# led_board.net
KiCad netlist of a schematic drawn in EAGLE
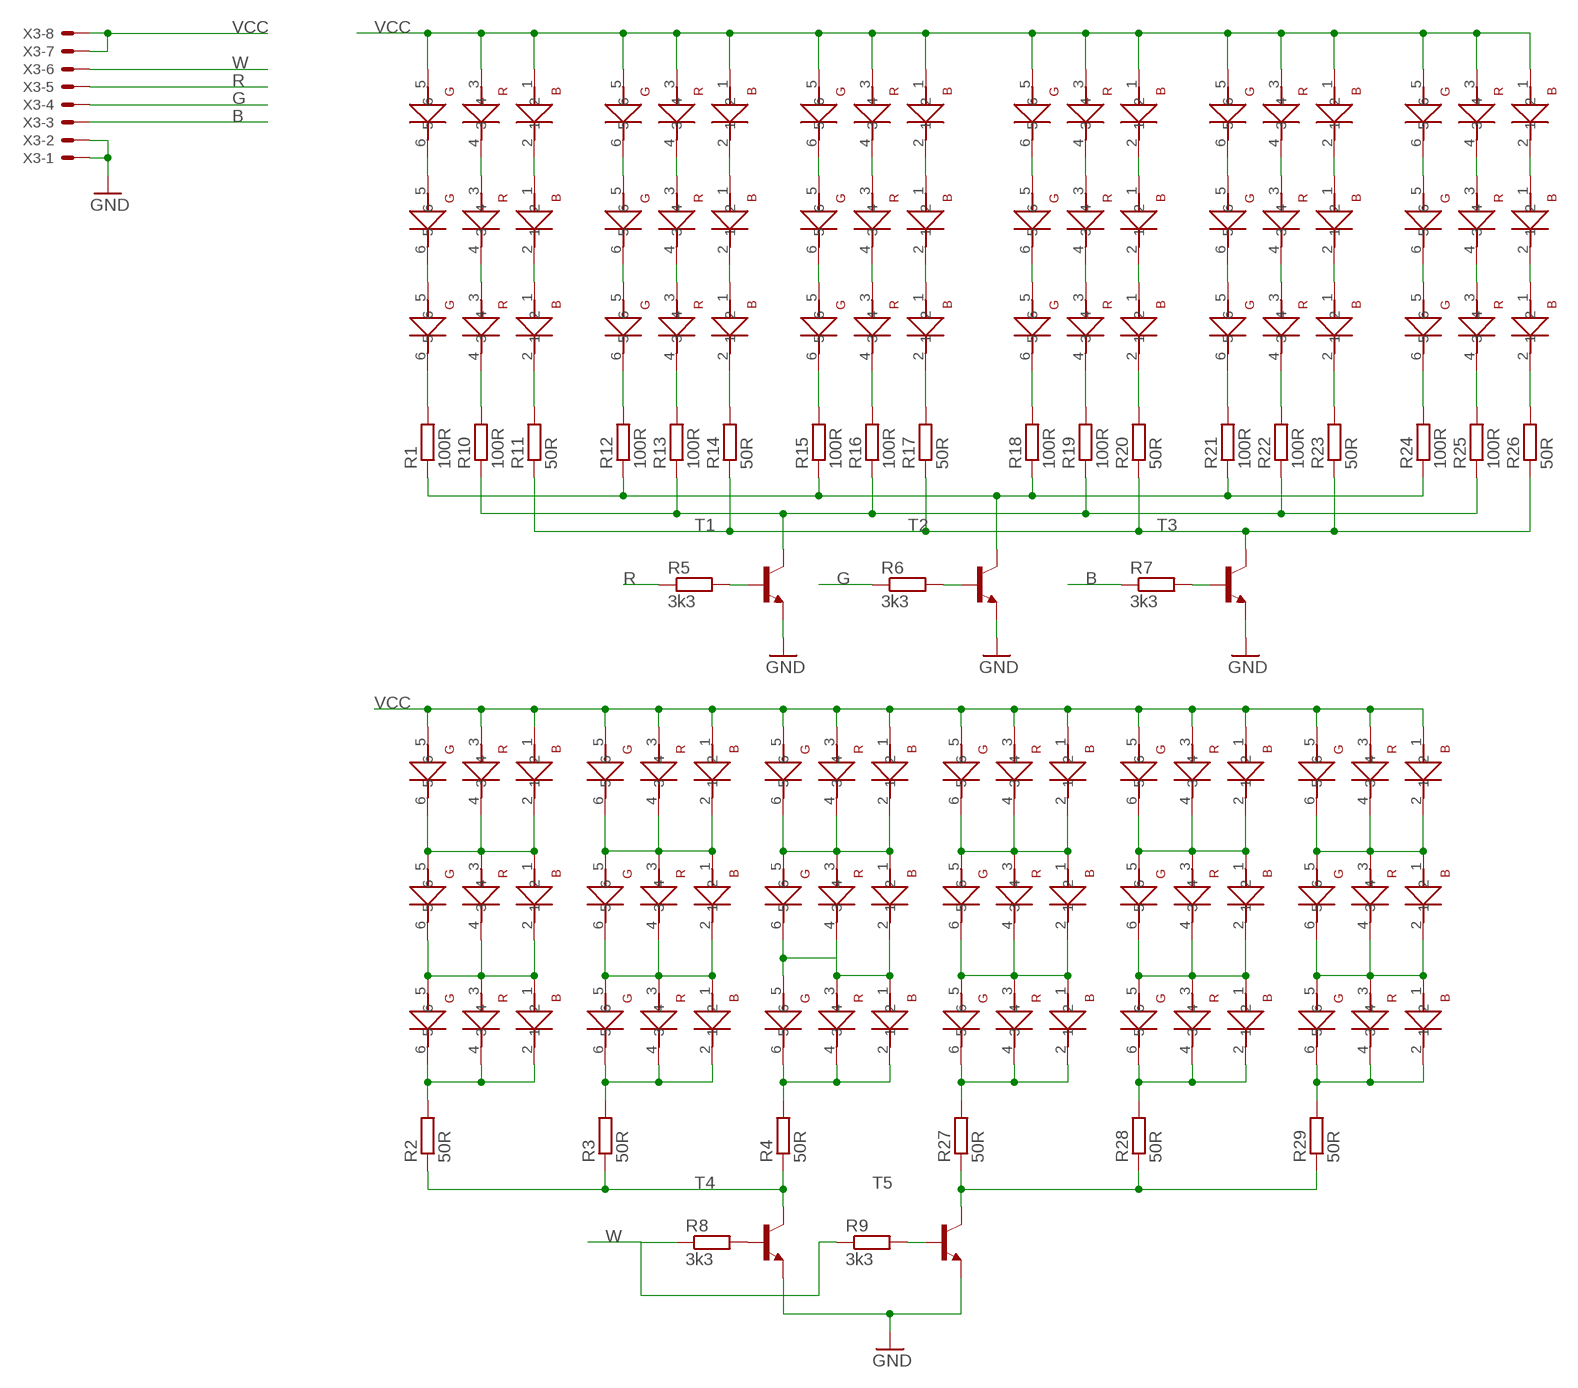
[diagram p0: schematic, sheet 1]

(export (version "E")
  (design (tool "Eeschema 10.0.6"))
  (components
    (comp (ref "R1")
      (value "100R")
      (footprint "eagle-import:M1206")
      (libsource (lib "eagle-import") (part "R-EU_M1206"))
    )
    (comp (ref "R2")
      (value "50R")
      (footprint "eagle-import:M1206")
      (libsource (lib "eagle-import") (part "R-EU_M1206"))
    )
    (comp (ref "R3")
      (value "50R")
      (footprint "eagle-import:M1206")
      (libsource (lib "eagle-import") (part "R-EU_M1206"))
    )
    (comp (ref "R4")
      (value "50R")
      (footprint "eagle-import:M1206")
      (libsource (lib "eagle-import") (part "R-EU_M1206"))
    )
    (comp (ref "R5")
      (value "3k3")
      (footprint "eagle-import:M1206")
      (libsource (lib "eagle-import") (part "R-EU_M1206"))
    )
    (comp (ref "R6")
      (value "3k3")
      (footprint "eagle-import:M1206")
      (libsource (lib "eagle-import") (part "R-EU_M1206"))
    )
    (comp (ref "R7")
      (value "3k3")
      (footprint "eagle-import:M1206")
      (libsource (lib "eagle-import") (part "R-EU_M1206"))
    )
    (comp (ref "R8")
      (value "3k3")
      (footprint "eagle-import:M1206")
      (libsource (lib "eagle-import") (part "R-EU_M1206"))
    )
    (comp (ref "R9")
      (value "3k3")
      (footprint "eagle-import:M1206")
      (libsource (lib "eagle-import") (part "R-EU_M1206"))
    )
    (comp (ref "R10")
      (value "100R")
      (footprint "eagle-import:M1206")
      (libsource (lib "eagle-import") (part "R-EU_M1206"))
    )
    (comp (ref "R11")
      (value "50R")
      (footprint "eagle-import:M1206")
      (libsource (lib "eagle-import") (part "R-EU_M1206"))
    )
    (comp (ref "R12")
      (value "100R")
      (footprint "eagle-import:M1206")
      (libsource (lib "eagle-import") (part "R-EU_M1206"))
    )
    (comp (ref "R13")
      (value "100R")
      (footprint "eagle-import:M1206")
      (libsource (lib "eagle-import") (part "R-EU_M1206"))
    )
    (comp (ref "R14")
      (value "50R")
      (footprint "eagle-import:M1206")
      (libsource (lib "eagle-import") (part "R-EU_M1206"))
    )
    (comp (ref "R15")
      (value "100R")
      (footprint "eagle-import:M1206")
      (libsource (lib "eagle-import") (part "R-EU_M1206"))
    )
    (comp (ref "R16")
      (value "100R")
      (footprint "eagle-import:M1206")
      (libsource (lib "eagle-import") (part "R-EU_M1206"))
    )
    (comp (ref "R17")
      (value "50R")
      (footprint "eagle-import:M1206")
      (libsource (lib "eagle-import") (part "R-EU_M1206"))
    )
    (comp (ref "R18")
      (value "100R")
      (footprint "eagle-import:M1206")
      (libsource (lib "eagle-import") (part "R-EU_M1206"))
    )
    (comp (ref "R19")
      (value "100R")
      (footprint "eagle-import:M1206")
      (libsource (lib "eagle-import") (part "R-EU_M1206"))
    )
    (comp (ref "R20")
      (value "50R")
      (footprint "eagle-import:M1206")
      (libsource (lib "eagle-import") (part "R-EU_M1206"))
    )
    (comp (ref "R21")
      (value "100R")
      (footprint "eagle-import:M1206")
      (libsource (lib "eagle-import") (part "R-EU_M1206"))
    )
    (comp (ref "R22")
      (value "100R")
      (footprint "eagle-import:M1206")
      (libsource (lib "eagle-import") (part "R-EU_M1206"))
    )
    (comp (ref "R23")
      (value "50R")
      (footprint "eagle-import:M1206")
      (libsource (lib "eagle-import") (part "R-EU_M1206"))
    )
    (comp (ref "R24")
      (value "100R")
      (footprint "eagle-import:M1206")
      (libsource (lib "eagle-import") (part "R-EU_M1206"))
    )
    (comp (ref "R25")
      (value "100R")
      (footprint "eagle-import:M1206")
      (libsource (lib "eagle-import") (part "R-EU_M1206"))
    )
    (comp (ref "R26")
      (value "50R")
      (footprint "eagle-import:M1206")
      (libsource (lib "eagle-import") (part "R-EU_M1206"))
    )
    (comp (ref "R27")
      (value "50R")
      (footprint "eagle-import:M1206")
      (libsource (lib "eagle-import") (part "R-EU_M1206"))
    )
    (comp (ref "R28")
      (value "50R")
      (footprint "eagle-import:M1206")
      (libsource (lib "eagle-import") (part "R-EU_M1206"))
    )
    (comp (ref "R29")
      (value "50R")
      (footprint "eagle-import:M1206")
      (libsource (lib "eagle-import") (part "R-EU_M1206"))
    )
    (comp (ref "T1")
      (value "-NPN-SOT223")
      (footprint "eagle-import:SOT223")
      (libsource (lib "eagle-import") (part "-NPN-SOT223"))
    )
    (comp (ref "T2")
      (value "-NPN-SOT223")
      (footprint "eagle-import:SOT223")
      (libsource (lib "eagle-import") (part "-NPN-SOT223"))
    )
    (comp (ref "T3")
      (value "-NPN-SOT223")
      (footprint "eagle-import:SOT223")
      (libsource (lib "eagle-import") (part "-NPN-SOT223"))
    )
    (comp (ref "T4")
      (value "-NPN-SOT223")
      (footprint "eagle-import:SOT223")
      (libsource (lib "eagle-import") (part "-NPN-SOT223"))
    )
    (comp (ref "T5")
      (value "-NPN-SOT223")
      (footprint "eagle-import:SOT223")
      (libsource (lib "eagle-import") (part "-NPN-SOT223"))
    )
    (comp (ref "U$1")
      (value "5050_LED")
      (footprint "eagle-import:5050_LED")
      (libsource (lib "eagle-import") (part "5050_LED"))
    )
    (comp (ref "U$2")
      (value "5050_LED")
      (footprint "eagle-import:5050_LED")
      (libsource (lib "eagle-import") (part "5050_LED"))
    )
    (comp (ref "U$3")
      (value "5050_LED")
      (footprint "eagle-import:5050_LED")
      (libsource (lib "eagle-import") (part "5050_LED"))
    )
    (comp (ref "U$4")
      (value "5050_LED")
      (footprint "eagle-import:5050_LED")
      (libsource (lib "eagle-import") (part "5050_LED"))
    )
    (comp (ref "U$5")
      (value "5050_LED")
      (footprint "eagle-import:5050_LED")
      (libsource (lib "eagle-import") (part "5050_LED"))
    )
    (comp (ref "U$6")
      (value "5050_LED")
      (footprint "eagle-import:5050_LED")
      (libsource (lib "eagle-import") (part "5050_LED"))
    )
    (comp (ref "U$7")
      (value "5050_LED")
      (footprint "eagle-import:5050_LED")
      (libsource (lib "eagle-import") (part "5050_LED"))
    )
    (comp (ref "U$8")
      (value "5050_LED")
      (footprint "eagle-import:5050_LED")
      (libsource (lib "eagle-import") (part "5050_LED"))
    )
    (comp (ref "U$9")
      (value "5050_LED")
      (footprint "eagle-import:5050_LED")
      (libsource (lib "eagle-import") (part "5050_LED"))
    )
    (comp (ref "U$10")
      (value "5050_LED")
      (footprint "eagle-import:5050_LED")
      (libsource (lib "eagle-import") (part "5050_LED"))
    )
    (comp (ref "U$11")
      (value "5050_LED")
      (footprint "eagle-import:5050_LED")
      (libsource (lib "eagle-import") (part "5050_LED"))
    )
    (comp (ref "U$12")
      (value "5050_LED")
      (footprint "eagle-import:5050_LED")
      (libsource (lib "eagle-import") (part "5050_LED"))
    )
    (comp (ref "U$13")
      (value "5050_LED")
      (footprint "eagle-import:5050_LED")
      (libsource (lib "eagle-import") (part "5050_LED"))
    )
    (comp (ref "U$14")
      (value "5050_LED")
      (footprint "eagle-import:5050_LED")
      (libsource (lib "eagle-import") (part "5050_LED"))
    )
    (comp (ref "U$15")
      (value "5050_LED")
      (footprint "eagle-import:5050_LED")
      (libsource (lib "eagle-import") (part "5050_LED"))
    )
    (comp (ref "U$16")
      (value "5050_LED")
      (footprint "eagle-import:5050_LED")
      (libsource (lib "eagle-import") (part "5050_LED"))
    )
    (comp (ref "U$17")
      (value "5050_LED")
      (footprint "eagle-import:5050_LED")
      (libsource (lib "eagle-import") (part "5050_LED"))
    )
    (comp (ref "U$18")
      (value "5050_LED")
      (footprint "eagle-import:5050_LED")
      (libsource (lib "eagle-import") (part "5050_LED"))
    )
    (comp (ref "U$19")
      (value "5050_LED")
      (footprint "eagle-import:5050_LED")
      (libsource (lib "eagle-import") (part "5050_LED"))
    )
    (comp (ref "U$20")
      (value "5050_LED")
      (footprint "eagle-import:5050_LED")
      (libsource (lib "eagle-import") (part "5050_LED"))
    )
    (comp (ref "U$21")
      (value "5050_LED")
      (footprint "eagle-import:5050_LED")
      (libsource (lib "eagle-import") (part "5050_LED"))
    )
    (comp (ref "U$22")
      (value "5050_LED")
      (footprint "eagle-import:5050_LED")
      (libsource (lib "eagle-import") (part "5050_LED"))
    )
    (comp (ref "U$23")
      (value "5050_LED")
      (footprint "eagle-import:5050_LED")
      (libsource (lib "eagle-import") (part "5050_LED"))
    )
    (comp (ref "U$24")
      (value "5050_LED")
      (footprint "eagle-import:5050_LED")
      (libsource (lib "eagle-import") (part "5050_LED"))
    )
    (comp (ref "U$25")
      (value "5050_LED")
      (footprint "eagle-import:5050_LED")
      (libsource (lib "eagle-import") (part "5050_LED"))
    )
    (comp (ref "U$26")
      (value "5050_LED")
      (footprint "eagle-import:5050_LED")
      (libsource (lib "eagle-import") (part "5050_LED"))
    )
    (comp (ref "U$27")
      (value "5050_LED")
      (footprint "eagle-import:5050_LED")
      (libsource (lib "eagle-import") (part "5050_LED"))
    )
    (comp (ref "U$28")
      (value "5050_LED")
      (footprint "eagle-import:5050_LED")
      (libsource (lib "eagle-import") (part "5050_LED"))
    )
    (comp (ref "U$29")
      (value "5050_LED")
      (footprint "eagle-import:5050_LED")
      (libsource (lib "eagle-import") (part "5050_LED"))
    )
    (comp (ref "U$30")
      (value "5050_LED")
      (footprint "eagle-import:5050_LED")
      (libsource (lib "eagle-import") (part "5050_LED"))
    )
    (comp (ref "U$31")
      (value "5050_LED")
      (footprint "eagle-import:5050_LED")
      (libsource (lib "eagle-import") (part "5050_LED"))
    )
    (comp (ref "U$32")
      (value "5050_LED")
      (footprint "eagle-import:5050_LED")
      (libsource (lib "eagle-import") (part "5050_LED"))
    )
    (comp (ref "U$33")
      (value "5050_LED")
      (footprint "eagle-import:5050_LED")
      (libsource (lib "eagle-import") (part "5050_LED"))
    )
    (comp (ref "U$34")
      (value "5050_LED")
      (footprint "eagle-import:5050_LED")
      (libsource (lib "eagle-import") (part "5050_LED"))
    )
    (comp (ref "U$35")
      (value "5050_LED")
      (footprint "eagle-import:5050_LED")
      (libsource (lib "eagle-import") (part "5050_LED"))
    )
    (comp (ref "U$38")
      (value "5050_LED")
      (footprint "eagle-import:5050_LED")
      (libsource (lib "eagle-import") (part "5050_LED"))
    )
    (comp (ref "X3")
      (value "KK-156-8")
      (footprint "eagle-import:KK-156-8")
      (fields (field (name "MF") "MOLEX"))
      (libsource (lib "eagle-import") (part "KK-156-8"))
    )
  )
  (nets
    (net (code "1") (name "/B") (class "Default")
      (node (ref "R7") (pin "1") (pinfunction "1_1") (pintype "passive"))
      (node (ref "X3") (pin "3") (pinfunction "S_3") (pintype "passive"))
    )
    (net (code "2") (name "/G") (class "Default")
      (node (ref "R6") (pin "1") (pinfunction "1_1") (pintype "passive"))
      (node (ref "X3") (pin "4") (pinfunction "S_4") (pintype "passive"))
    )
    (net (code "3") (name "/R") (class "Default")
      (node (ref "R5") (pin "1") (pinfunction "1_1") (pintype "passive"))
      (node (ref "X3") (pin "5") (pinfunction "S_5") (pintype "passive"))
    )
    (net (code "4") (name "/VCC") (class "Default")
      (node (ref "U$11") (pin "1") (pinfunction "1_1") (pintype "bidirectional"))
      (node (ref "U$11") (pin "3") (pinfunction "3_3") (pintype "bidirectional"))
      (node (ref "U$11") (pin "5") (pinfunction "5_5") (pintype "bidirectional"))
      (node (ref "U$14") (pin "1") (pinfunction "1_1") (pintype "bidirectional"))
      (node (ref "U$14") (pin "3") (pinfunction "3_3") (pintype "bidirectional"))
      (node (ref "U$14") (pin "5") (pinfunction "5_5") (pintype "bidirectional"))
      (node (ref "U$17") (pin "1") (pinfunction "1_1") (pintype "bidirectional"))
      (node (ref "U$17") (pin "3") (pinfunction "3_3") (pintype "bidirectional"))
      (node (ref "U$17") (pin "5") (pinfunction "5_5") (pintype "bidirectional"))
      (node (ref "U$18") (pin "1") (pinfunction "1_1") (pintype "bidirectional"))
      (node (ref "U$18") (pin "3") (pinfunction "3_3") (pintype "bidirectional"))
      (node (ref "U$18") (pin "5") (pinfunction "5_5") (pintype "bidirectional"))
      (node (ref "U$19") (pin "1") (pinfunction "1_1") (pintype "bidirectional"))
      (node (ref "U$19") (pin "3") (pinfunction "3_3") (pintype "bidirectional"))
      (node (ref "U$19") (pin "5") (pinfunction "5_5") (pintype "bidirectional"))
      (node (ref "U$2") (pin "1") (pinfunction "1_1") (pintype "bidirectional"))
      (node (ref "U$2") (pin "3") (pinfunction "3_3") (pintype "bidirectional"))
      (node (ref "U$2") (pin "5") (pinfunction "5_5") (pintype "bidirectional"))
      (node (ref "U$20") (pin "1") (pinfunction "1_1") (pintype "bidirectional"))
      (node (ref "U$20") (pin "3") (pinfunction "3_3") (pintype "bidirectional"))
      (node (ref "U$20") (pin "5") (pinfunction "5_5") (pintype "bidirectional"))
      (node (ref "U$21") (pin "1") (pinfunction "1_1") (pintype "bidirectional"))
      (node (ref "U$21") (pin "3") (pinfunction "3_3") (pintype "bidirectional"))
      (node (ref "U$21") (pin "5") (pinfunction "5_5") (pintype "bidirectional"))
      (node (ref "U$22") (pin "1") (pinfunction "1_1") (pintype "bidirectional"))
      (node (ref "U$22") (pin "3") (pinfunction "3_3") (pintype "bidirectional"))
      (node (ref "U$22") (pin "5") (pinfunction "5_5") (pintype "bidirectional"))
      (node (ref "U$34") (pin "1") (pinfunction "1_1") (pintype "bidirectional"))
      (node (ref "U$34") (pin "3") (pinfunction "3_3") (pintype "bidirectional"))
      (node (ref "U$34") (pin "5") (pinfunction "5_5") (pintype "bidirectional"))
      (node (ref "U$5") (pin "1") (pinfunction "1_1") (pintype "bidirectional"))
      (node (ref "U$5") (pin "3") (pinfunction "3_3") (pintype "bidirectional"))
      (node (ref "U$5") (pin "5") (pinfunction "5_5") (pintype "bidirectional"))
      (node (ref "U$8") (pin "1") (pinfunction "1_1") (pintype "bidirectional"))
      (node (ref "U$8") (pin "3") (pinfunction "3_3") (pintype "bidirectional"))
      (node (ref "U$8") (pin "5") (pinfunction "5_5") (pintype "bidirectional"))
      (node (ref "X3") (pin "7") (pinfunction "S_7") (pintype "passive"))
      (node (ref "X3") (pin "8") (pinfunction "S_8") (pintype "passive"))
    )
    (net (code "5") (name "/W") (class "Default")
      (node (ref "R8") (pin "1") (pinfunction "1_1") (pintype "passive"))
      (node (ref "R9") (pin "1") (pinfunction "1_1") (pintype "passive"))
      (node (ref "X3") (pin "6") (pinfunction "S_6") (pintype "passive"))
    )
    (net (code "6") (name "GND") (class "Default")
      (node (ref "T1") (pin "3") (pinfunction "E_3") (pintype "passive"))
      (node (ref "T2") (pin "3") (pinfunction "E_3") (pintype "passive"))
      (node (ref "T3") (pin "3") (pinfunction "E_3") (pintype "passive"))
      (node (ref "T4") (pin "3") (pinfunction "E_3") (pintype "passive"))
      (node (ref "T5") (pin "3") (pinfunction "E_3") (pintype "passive"))
      (node (ref "X3") (pin "1") (pinfunction "S_1") (pintype "passive"))
      (node (ref "X3") (pin "2") (pinfunction "S_2") (pintype "passive"))
    )
    (net (code "7") (name "Net-(R1-Pad2)") (class "Default")
      (node (ref "R1") (pin "2") (pinfunction "2_2") (pintype "passive"))
      (node (ref "U$1") (pin "6") (pinfunction "6_6") (pintype "bidirectional"))
    )
    (net (code "8") (name "Net-(R2-Pad2)") (class "Default")
      (node (ref "R2") (pin "2") (pinfunction "2_2") (pintype "passive"))
      (node (ref "U$29") (pin "2") (pinfunction "2_2") (pintype "bidirectional"))
      (node (ref "U$29") (pin "4") (pinfunction "4_4") (pintype "bidirectional"))
      (node (ref "U$29") (pin "6") (pinfunction "6_6") (pintype "bidirectional"))
    )
    (net (code "9") (name "Net-(R3-Pad2)") (class "Default")
      (node (ref "R3") (pin "2") (pinfunction "2_2") (pintype "passive"))
      (node (ref "U$30") (pin "2") (pinfunction "2_2") (pintype "bidirectional"))
      (node (ref "U$30") (pin "4") (pinfunction "4_4") (pintype "bidirectional"))
      (node (ref "U$30") (pin "6") (pinfunction "6_6") (pintype "bidirectional"))
    )
    (net (code "10") (name "Net-(R4-Pad2)") (class "Default")
      (node (ref "R4") (pin "2") (pinfunction "2_2") (pintype "passive"))
      (node (ref "U$31") (pin "2") (pinfunction "2_2") (pintype "bidirectional"))
      (node (ref "U$31") (pin "4") (pinfunction "4_4") (pintype "bidirectional"))
      (node (ref "U$31") (pin "6") (pinfunction "6_6") (pintype "bidirectional"))
    )
    (net (code "11") (name "Net-(R10-Pad2)") (class "Default")
      (node (ref "R10") (pin "2") (pinfunction "2_2") (pintype "passive"))
      (node (ref "U$1") (pin "4") (pinfunction "4_4") (pintype "bidirectional"))
    )
    (net (code "12") (name "Net-(R11-Pad2)") (class "Default")
      (node (ref "R11") (pin "2") (pinfunction "2_2") (pintype "passive"))
      (node (ref "U$1") (pin "2") (pinfunction "2_2") (pintype "bidirectional"))
    )
    (net (code "13") (name "Net-(R12-Pad2)") (class "Default")
      (node (ref "R12") (pin "2") (pinfunction "2_2") (pintype "passive"))
      (node (ref "U$4") (pin "6") (pinfunction "6_6") (pintype "bidirectional"))
    )
    (net (code "14") (name "Net-(R13-Pad2)") (class "Default")
      (node (ref "R13") (pin "2") (pinfunction "2_2") (pintype "passive"))
      (node (ref "U$4") (pin "4") (pinfunction "4_4") (pintype "bidirectional"))
    )
    (net (code "15") (name "Net-(R14-Pad2)") (class "Default")
      (node (ref "R14") (pin "2") (pinfunction "2_2") (pintype "passive"))
      (node (ref "U$4") (pin "2") (pinfunction "2_2") (pintype "bidirectional"))
    )
    (net (code "16") (name "Net-(R15-Pad2)") (class "Default")
      (node (ref "R15") (pin "2") (pinfunction "2_2") (pintype "passive"))
      (node (ref "U$7") (pin "6") (pinfunction "6_6") (pintype "bidirectional"))
    )
    (net (code "17") (name "Net-(R16-Pad2)") (class "Default")
      (node (ref "R16") (pin "2") (pinfunction "2_2") (pintype "passive"))
      (node (ref "U$7") (pin "4") (pinfunction "4_4") (pintype "bidirectional"))
    )
    (net (code "18") (name "Net-(R17-Pad2)") (class "Default")
      (node (ref "R17") (pin "2") (pinfunction "2_2") (pintype "passive"))
      (node (ref "U$7") (pin "2") (pinfunction "2_2") (pintype "bidirectional"))
    )
    (net (code "19") (name "Net-(R18-Pad2)") (class "Default")
      (node (ref "R18") (pin "2") (pinfunction "2_2") (pintype "passive"))
      (node (ref "U$10") (pin "6") (pinfunction "6_6") (pintype "bidirectional"))
    )
    (net (code "20") (name "Net-(R19-Pad2)") (class "Default")
      (node (ref "R19") (pin "2") (pinfunction "2_2") (pintype "passive"))
      (node (ref "U$10") (pin "4") (pinfunction "4_4") (pintype "bidirectional"))
    )
    (net (code "21") (name "Net-(R20-Pad2)") (class "Default")
      (node (ref "R20") (pin "2") (pinfunction "2_2") (pintype "passive"))
      (node (ref "U$10") (pin "2") (pinfunction "2_2") (pintype "bidirectional"))
    )
    (net (code "22") (name "Net-(R21-Pad2)") (class "Default")
      (node (ref "R21") (pin "2") (pinfunction "2_2") (pintype "passive"))
      (node (ref "U$13") (pin "6") (pinfunction "6_6") (pintype "bidirectional"))
    )
    (net (code "23") (name "Net-(R22-Pad2)") (class "Default")
      (node (ref "R22") (pin "2") (pinfunction "2_2") (pintype "passive"))
      (node (ref "U$13") (pin "4") (pinfunction "4_4") (pintype "bidirectional"))
    )
    (net (code "24") (name "Net-(R23-Pad2)") (class "Default")
      (node (ref "R23") (pin "2") (pinfunction "2_2") (pintype "passive"))
      (node (ref "U$13") (pin "2") (pinfunction "2_2") (pintype "bidirectional"))
    )
    (net (code "25") (name "Net-(R24-Pad2)") (class "Default")
      (node (ref "R24") (pin "2") (pinfunction "2_2") (pintype "passive"))
      (node (ref "U$16") (pin "6") (pinfunction "6_6") (pintype "bidirectional"))
    )
    (net (code "26") (name "Net-(R25-Pad2)") (class "Default")
      (node (ref "R25") (pin "2") (pinfunction "2_2") (pintype "passive"))
      (node (ref "U$16") (pin "4") (pinfunction "4_4") (pintype "bidirectional"))
    )
    (net (code "27") (name "Net-(R26-Pad2)") (class "Default")
      (node (ref "R26") (pin "2") (pinfunction "2_2") (pintype "passive"))
      (node (ref "U$16") (pin "2") (pinfunction "2_2") (pintype "bidirectional"))
    )
    (net (code "28") (name "Net-(R27-Pad2)") (class "Default")
      (node (ref "R27") (pin "2") (pinfunction "2_2") (pintype "passive"))
      (node (ref "U$32") (pin "2") (pinfunction "2_2") (pintype "bidirectional"))
      (node (ref "U$32") (pin "4") (pinfunction "4_4") (pintype "bidirectional"))
      (node (ref "U$32") (pin "6") (pinfunction "6_6") (pintype "bidirectional"))
    )
    (net (code "29") (name "Net-(R28-Pad2)") (class "Default")
      (node (ref "R28") (pin "2") (pinfunction "2_2") (pintype "passive"))
      (node (ref "U$33") (pin "2") (pinfunction "2_2") (pintype "bidirectional"))
      (node (ref "U$33") (pin "4") (pinfunction "4_4") (pintype "bidirectional"))
      (node (ref "U$33") (pin "6") (pinfunction "6_6") (pintype "bidirectional"))
    )
    (net (code "30") (name "Net-(R29-Pad2)") (class "Default")
      (node (ref "R29") (pin "2") (pinfunction "2_2") (pintype "passive"))
      (node (ref "U$35") (pin "2") (pinfunction "2_2") (pintype "bidirectional"))
      (node (ref "U$35") (pin "4") (pinfunction "4_4") (pintype "bidirectional"))
      (node (ref "U$35") (pin "6") (pinfunction "6_6") (pintype "bidirectional"))
    )
    (net (code "31") (name "Net-(T1-B)") (class "Default")
      (node (ref "R5") (pin "2") (pinfunction "2_2") (pintype "passive"))
      (node (ref "T1") (pin "1") (pinfunction "B_1") (pintype "passive"))
    )
    (net (code "32") (name "Net-(T1-C)") (class "Default")
      (node (ref "R10") (pin "1") (pinfunction "1_1") (pintype "passive"))
      (node (ref "R13") (pin "1") (pinfunction "1_1") (pintype "passive"))
      (node (ref "R16") (pin "1") (pinfunction "1_1") (pintype "passive"))
      (node (ref "R19") (pin "1") (pinfunction "1_1") (pintype "passive"))
      (node (ref "R22") (pin "1") (pinfunction "1_1") (pintype "passive"))
      (node (ref "R25") (pin "1") (pinfunction "1_1") (pintype "passive"))
      (node (ref "T1") (pin "4") (pinfunction "C_4") (pintype "passive"))
    )
    (net (code "33") (name "Net-(T2-B)") (class "Default")
      (node (ref "R6") (pin "2") (pinfunction "2_2") (pintype "passive"))
      (node (ref "T2") (pin "1") (pinfunction "B_1") (pintype "passive"))
    )
    (net (code "34") (name "Net-(T2-C)") (class "Default")
      (node (ref "R1") (pin "1") (pinfunction "1_1") (pintype "passive"))
      (node (ref "R12") (pin "1") (pinfunction "1_1") (pintype "passive"))
      (node (ref "R15") (pin "1") (pinfunction "1_1") (pintype "passive"))
      (node (ref "R18") (pin "1") (pinfunction "1_1") (pintype "passive"))
      (node (ref "R21") (pin "1") (pinfunction "1_1") (pintype "passive"))
      (node (ref "R24") (pin "1") (pinfunction "1_1") (pintype "passive"))
      (node (ref "T2") (pin "4") (pinfunction "C_4") (pintype "passive"))
    )
    (net (code "35") (name "Net-(T3-B)") (class "Default")
      (node (ref "R7") (pin "2") (pinfunction "2_2") (pintype "passive"))
      (node (ref "T3") (pin "1") (pinfunction "B_1") (pintype "passive"))
    )
    (net (code "36") (name "Net-(T3-C)") (class "Default")
      (node (ref "R11") (pin "1") (pinfunction "1_1") (pintype "passive"))
      (node (ref "R14") (pin "1") (pinfunction "1_1") (pintype "passive"))
      (node (ref "R17") (pin "1") (pinfunction "1_1") (pintype "passive"))
      (node (ref "R20") (pin "1") (pinfunction "1_1") (pintype "passive"))
      (node (ref "R23") (pin "1") (pinfunction "1_1") (pintype "passive"))
      (node (ref "R26") (pin "1") (pinfunction "1_1") (pintype "passive"))
      (node (ref "T3") (pin "4") (pinfunction "C_4") (pintype "passive"))
    )
    (net (code "37") (name "Net-(T4-B)") (class "Default")
      (node (ref "R8") (pin "2") (pinfunction "2_2") (pintype "passive"))
      (node (ref "T4") (pin "1") (pinfunction "B_1") (pintype "passive"))
    )
    (net (code "38") (name "Net-(T4-C)") (class "Default")
      (node (ref "R2") (pin "1") (pinfunction "1_1") (pintype "passive"))
      (node (ref "R3") (pin "1") (pinfunction "1_1") (pintype "passive"))
      (node (ref "R4") (pin "1") (pinfunction "1_1") (pintype "passive"))
      (node (ref "T4") (pin "4") (pinfunction "C_4") (pintype "passive"))
    )
    (net (code "39") (name "Net-(T5-B)") (class "Default")
      (node (ref "R9") (pin "2") (pinfunction "2_2") (pintype "passive"))
      (node (ref "T5") (pin "1") (pinfunction "B_1") (pintype "passive"))
    )
    (net (code "40") (name "Net-(T5-C)") (class "Default")
      (node (ref "R27") (pin "1") (pinfunction "1_1") (pintype "passive"))
      (node (ref "R28") (pin "1") (pinfunction "1_1") (pintype "passive"))
      (node (ref "R29") (pin "1") (pinfunction "1_1") (pintype "passive"))
      (node (ref "T5") (pin "4") (pinfunction "C_4") (pintype "passive"))
    )
    (net (code "41") (name "Net-(U$1-Pad1)") (class "Default")
      (node (ref "U$1") (pin "1") (pinfunction "1_1") (pintype "bidirectional"))
      (node (ref "U$38") (pin "2") (pinfunction "2_2") (pintype "bidirectional"))
    )
    (net (code "42") (name "Net-(U$1-Pad3)") (class "Default")
      (node (ref "U$1") (pin "3") (pinfunction "3_3") (pintype "bidirectional"))
      (node (ref "U$38") (pin "4") (pinfunction "4_4") (pintype "bidirectional"))
    )
    (net (code "43") (name "Net-(U$1-Pad5)") (class "Default")
      (node (ref "U$1") (pin "5") (pinfunction "5_5") (pintype "bidirectional"))
      (node (ref "U$38") (pin "6") (pinfunction "6_6") (pintype "bidirectional"))
    )
    (net (code "44") (name "Net-(U$2-Pad2)") (class "Default")
      (node (ref "U$2") (pin "2") (pinfunction "2_2") (pintype "bidirectional"))
      (node (ref "U$3") (pin "1") (pinfunction "1_1") (pintype "bidirectional"))
    )
    (net (code "45") (name "Net-(U$2-Pad4)") (class "Default")
      (node (ref "U$2") (pin "4") (pinfunction "4_4") (pintype "bidirectional"))
      (node (ref "U$3") (pin "3") (pinfunction "3_3") (pintype "bidirectional"))
    )
    (net (code "46") (name "Net-(U$2-Pad6)") (class "Default")
      (node (ref "U$2") (pin "6") (pinfunction "6_6") (pintype "bidirectional"))
      (node (ref "U$3") (pin "5") (pinfunction "5_5") (pintype "bidirectional"))
    )
    (net (code "47") (name "Net-(U$3-Pad2)") (class "Default")
      (node (ref "U$3") (pin "2") (pinfunction "2_2") (pintype "bidirectional"))
      (node (ref "U$4") (pin "1") (pinfunction "1_1") (pintype "bidirectional"))
    )
    (net (code "48") (name "Net-(U$3-Pad4)") (class "Default")
      (node (ref "U$3") (pin "4") (pinfunction "4_4") (pintype "bidirectional"))
      (node (ref "U$4") (pin "3") (pinfunction "3_3") (pintype "bidirectional"))
    )
    (net (code "49") (name "Net-(U$3-Pad6)") (class "Default")
      (node (ref "U$3") (pin "6") (pinfunction "6_6") (pintype "bidirectional"))
      (node (ref "U$4") (pin "5") (pinfunction "5_5") (pintype "bidirectional"))
    )
    (net (code "50") (name "Net-(U$5-Pad2)") (class "Default")
      (node (ref "U$5") (pin "2") (pinfunction "2_2") (pintype "bidirectional"))
      (node (ref "U$6") (pin "1") (pinfunction "1_1") (pintype "bidirectional"))
    )
    (net (code "51") (name "Net-(U$5-Pad4)") (class "Default")
      (node (ref "U$5") (pin "4") (pinfunction "4_4") (pintype "bidirectional"))
      (node (ref "U$6") (pin "3") (pinfunction "3_3") (pintype "bidirectional"))
    )
    (net (code "52") (name "Net-(U$5-Pad6)") (class "Default")
      (node (ref "U$5") (pin "6") (pinfunction "6_6") (pintype "bidirectional"))
      (node (ref "U$6") (pin "5") (pinfunction "5_5") (pintype "bidirectional"))
    )
    (net (code "53") (name "Net-(U$6-Pad2)") (class "Default")
      (node (ref "U$6") (pin "2") (pinfunction "2_2") (pintype "bidirectional"))
      (node (ref "U$7") (pin "1") (pinfunction "1_1") (pintype "bidirectional"))
    )
    (net (code "54") (name "Net-(U$6-Pad4)") (class "Default")
      (node (ref "U$6") (pin "4") (pinfunction "4_4") (pintype "bidirectional"))
      (node (ref "U$7") (pin "3") (pinfunction "3_3") (pintype "bidirectional"))
    )
    (net (code "55") (name "Net-(U$6-Pad6)") (class "Default")
      (node (ref "U$6") (pin "6") (pinfunction "6_6") (pintype "bidirectional"))
      (node (ref "U$7") (pin "5") (pinfunction "5_5") (pintype "bidirectional"))
    )
    (net (code "56") (name "Net-(U$8-Pad2)") (class "Default")
      (node (ref "U$8") (pin "2") (pinfunction "2_2") (pintype "bidirectional"))
      (node (ref "U$9") (pin "1") (pinfunction "1_1") (pintype "bidirectional"))
    )
    (net (code "57") (name "Net-(U$8-Pad4)") (class "Default")
      (node (ref "U$8") (pin "4") (pinfunction "4_4") (pintype "bidirectional"))
      (node (ref "U$9") (pin "3") (pinfunction "3_3") (pintype "bidirectional"))
    )
    (net (code "58") (name "Net-(U$8-Pad6)") (class "Default")
      (node (ref "U$8") (pin "6") (pinfunction "6_6") (pintype "bidirectional"))
      (node (ref "U$9") (pin "5") (pinfunction "5_5") (pintype "bidirectional"))
    )
    (net (code "59") (name "Net-(U$10-Pad1)") (class "Default")
      (node (ref "U$10") (pin "1") (pinfunction "1_1") (pintype "bidirectional"))
      (node (ref "U$9") (pin "2") (pinfunction "2_2") (pintype "bidirectional"))
    )
    (net (code "60") (name "Net-(U$10-Pad3)") (class "Default")
      (node (ref "U$10") (pin "3") (pinfunction "3_3") (pintype "bidirectional"))
      (node (ref "U$9") (pin "4") (pinfunction "4_4") (pintype "bidirectional"))
    )
    (net (code "61") (name "Net-(U$10-Pad5)") (class "Default")
      (node (ref "U$10") (pin "5") (pinfunction "5_5") (pintype "bidirectional"))
      (node (ref "U$9") (pin "6") (pinfunction "6_6") (pintype "bidirectional"))
    )
    (net (code "62") (name "Net-(U$11-Pad2)") (class "Default")
      (node (ref "U$11") (pin "2") (pinfunction "2_2") (pintype "bidirectional"))
      (node (ref "U$12") (pin "1") (pinfunction "1_1") (pintype "bidirectional"))
    )
    (net (code "63") (name "Net-(U$11-Pad4)") (class "Default")
      (node (ref "U$11") (pin "4") (pinfunction "4_4") (pintype "bidirectional"))
      (node (ref "U$12") (pin "3") (pinfunction "3_3") (pintype "bidirectional"))
    )
    (net (code "64") (name "Net-(U$11-Pad6)") (class "Default")
      (node (ref "U$11") (pin "6") (pinfunction "6_6") (pintype "bidirectional"))
      (node (ref "U$12") (pin "5") (pinfunction "5_5") (pintype "bidirectional"))
    )
    (net (code "65") (name "Net-(U$12-Pad2)") (class "Default")
      (node (ref "U$12") (pin "2") (pinfunction "2_2") (pintype "bidirectional"))
      (node (ref "U$13") (pin "1") (pinfunction "1_1") (pintype "bidirectional"))
    )
    (net (code "66") (name "Net-(U$12-Pad4)") (class "Default")
      (node (ref "U$12") (pin "4") (pinfunction "4_4") (pintype "bidirectional"))
      (node (ref "U$13") (pin "3") (pinfunction "3_3") (pintype "bidirectional"))
    )
    (net (code "67") (name "Net-(U$12-Pad6)") (class "Default")
      (node (ref "U$12") (pin "6") (pinfunction "6_6") (pintype "bidirectional"))
      (node (ref "U$13") (pin "5") (pinfunction "5_5") (pintype "bidirectional"))
    )
    (net (code "68") (name "Net-(U$14-Pad2)") (class "Default")
      (node (ref "U$14") (pin "2") (pinfunction "2_2") (pintype "bidirectional"))
      (node (ref "U$15") (pin "1") (pinfunction "1_1") (pintype "bidirectional"))
    )
    (net (code "69") (name "Net-(U$14-Pad4)") (class "Default")
      (node (ref "U$14") (pin "4") (pinfunction "4_4") (pintype "bidirectional"))
      (node (ref "U$15") (pin "3") (pinfunction "3_3") (pintype "bidirectional"))
    )
    (net (code "70") (name "Net-(U$14-Pad6)") (class "Default")
      (node (ref "U$14") (pin "6") (pinfunction "6_6") (pintype "bidirectional"))
      (node (ref "U$15") (pin "5") (pinfunction "5_5") (pintype "bidirectional"))
    )
    (net (code "71") (name "Net-(U$15-Pad2)") (class "Default")
      (node (ref "U$15") (pin "2") (pinfunction "2_2") (pintype "bidirectional"))
      (node (ref "U$16") (pin "1") (pinfunction "1_1") (pintype "bidirectional"))
    )
    (net (code "72") (name "Net-(U$15-Pad4)") (class "Default")
      (node (ref "U$15") (pin "4") (pinfunction "4_4") (pintype "bidirectional"))
      (node (ref "U$16") (pin "3") (pinfunction "3_3") (pintype "bidirectional"))
    )
    (net (code "73") (name "Net-(U$15-Pad6)") (class "Default")
      (node (ref "U$15") (pin "6") (pinfunction "6_6") (pintype "bidirectional"))
      (node (ref "U$16") (pin "5") (pinfunction "5_5") (pintype "bidirectional"))
    )
    (net (code "74") (name "Net-(U$17-Pad2)") (class "Default")
      (node (ref "U$17") (pin "2") (pinfunction "2_2") (pintype "bidirectional"))
      (node (ref "U$17") (pin "4") (pinfunction "4_4") (pintype "bidirectional"))
      (node (ref "U$17") (pin "6") (pinfunction "6_6") (pintype "bidirectional"))
      (node (ref "U$23") (pin "1") (pinfunction "1_1") (pintype "bidirectional"))
      (node (ref "U$23") (pin "3") (pinfunction "3_3") (pintype "bidirectional"))
      (node (ref "U$23") (pin "5") (pinfunction "5_5") (pintype "bidirectional"))
    )
    (net (code "75") (name "Net-(U$18-Pad2)") (class "Default")
      (node (ref "U$18") (pin "2") (pinfunction "2_2") (pintype "bidirectional"))
      (node (ref "U$18") (pin "4") (pinfunction "4_4") (pintype "bidirectional"))
      (node (ref "U$18") (pin "6") (pinfunction "6_6") (pintype "bidirectional"))
      (node (ref "U$24") (pin "1") (pinfunction "1_1") (pintype "bidirectional"))
      (node (ref "U$24") (pin "3") (pinfunction "3_3") (pintype "bidirectional"))
      (node (ref "U$24") (pin "5") (pinfunction "5_5") (pintype "bidirectional"))
    )
    (net (code "76") (name "Net-(U$19-Pad2)") (class "Default")
      (node (ref "U$19") (pin "2") (pinfunction "2_2") (pintype "bidirectional"))
      (node (ref "U$19") (pin "4") (pinfunction "4_4") (pintype "bidirectional"))
      (node (ref "U$19") (pin "6") (pinfunction "6_6") (pintype "bidirectional"))
      (node (ref "U$25") (pin "1") (pinfunction "1_1") (pintype "bidirectional"))
      (node (ref "U$25") (pin "3") (pinfunction "3_3") (pintype "bidirectional"))
      (node (ref "U$25") (pin "5") (pinfunction "5_5") (pintype "bidirectional"))
    )
    (net (code "77") (name "Net-(U$20-Pad2)") (class "Default")
      (node (ref "U$20") (pin "2") (pinfunction "2_2") (pintype "bidirectional"))
      (node (ref "U$20") (pin "4") (pinfunction "4_4") (pintype "bidirectional"))
      (node (ref "U$20") (pin "6") (pinfunction "6_6") (pintype "bidirectional"))
      (node (ref "U$26") (pin "1") (pinfunction "1_1") (pintype "bidirectional"))
      (node (ref "U$26") (pin "3") (pinfunction "3_3") (pintype "bidirectional"))
      (node (ref "U$26") (pin "5") (pinfunction "5_5") (pintype "bidirectional"))
    )
    (net (code "78") (name "Net-(U$21-Pad2)") (class "Default")
      (node (ref "U$21") (pin "2") (pinfunction "2_2") (pintype "bidirectional"))
      (node (ref "U$21") (pin "4") (pinfunction "4_4") (pintype "bidirectional"))
      (node (ref "U$21") (pin "6") (pinfunction "6_6") (pintype "bidirectional"))
      (node (ref "U$27") (pin "1") (pinfunction "1_1") (pintype "bidirectional"))
      (node (ref "U$27") (pin "3") (pinfunction "3_3") (pintype "bidirectional"))
      (node (ref "U$27") (pin "5") (pinfunction "5_5") (pintype "bidirectional"))
    )
    (net (code "79") (name "Net-(U$22-Pad2)") (class "Default")
      (node (ref "U$22") (pin "2") (pinfunction "2_2") (pintype "bidirectional"))
      (node (ref "U$22") (pin "4") (pinfunction "4_4") (pintype "bidirectional"))
      (node (ref "U$22") (pin "6") (pinfunction "6_6") (pintype "bidirectional"))
      (node (ref "U$28") (pin "1") (pinfunction "1_1") (pintype "bidirectional"))
      (node (ref "U$28") (pin "3") (pinfunction "3_3") (pintype "bidirectional"))
      (node (ref "U$28") (pin "5") (pinfunction "5_5") (pintype "bidirectional"))
    )
    (net (code "80") (name "Net-(U$23-Pad2)") (class "Default")
      (node (ref "U$23") (pin "2") (pinfunction "2_2") (pintype "bidirectional"))
      (node (ref "U$23") (pin "4") (pinfunction "4_4") (pintype "bidirectional"))
      (node (ref "U$23") (pin "6") (pinfunction "6_6") (pintype "bidirectional"))
      (node (ref "U$29") (pin "1") (pinfunction "1_1") (pintype "bidirectional"))
      (node (ref "U$29") (pin "3") (pinfunction "3_3") (pintype "bidirectional"))
      (node (ref "U$29") (pin "5") (pinfunction "5_5") (pintype "bidirectional"))
    )
    (net (code "81") (name "Net-(U$24-Pad2)") (class "Default")
      (node (ref "U$24") (pin "2") (pinfunction "2_2") (pintype "bidirectional"))
      (node (ref "U$24") (pin "4") (pinfunction "4_4") (pintype "bidirectional"))
      (node (ref "U$24") (pin "6") (pinfunction "6_6") (pintype "bidirectional"))
      (node (ref "U$30") (pin "1") (pinfunction "1_1") (pintype "bidirectional"))
      (node (ref "U$30") (pin "3") (pinfunction "3_3") (pintype "bidirectional"))
      (node (ref "U$30") (pin "5") (pinfunction "5_5") (pintype "bidirectional"))
    )
    (net (code "82") (name "Net-(U$25-Pad2)") (class "Default")
      (node (ref "U$25") (pin "2") (pinfunction "2_2") (pintype "bidirectional"))
      (node (ref "U$25") (pin "4") (pinfunction "4_4") (pintype "bidirectional"))
      (node (ref "U$25") (pin "6") (pinfunction "6_6") (pintype "bidirectional"))
      (node (ref "U$31") (pin "1") (pinfunction "1_1") (pintype "bidirectional"))
      (node (ref "U$31") (pin "3") (pinfunction "3_3") (pintype "bidirectional"))
      (node (ref "U$31") (pin "5") (pinfunction "5_5") (pintype "bidirectional"))
    )
    (net (code "83") (name "Net-(U$26-Pad2)") (class "Default")
      (node (ref "U$26") (pin "2") (pinfunction "2_2") (pintype "bidirectional"))
      (node (ref "U$26") (pin "4") (pinfunction "4_4") (pintype "bidirectional"))
      (node (ref "U$26") (pin "6") (pinfunction "6_6") (pintype "bidirectional"))
      (node (ref "U$32") (pin "1") (pinfunction "1_1") (pintype "bidirectional"))
      (node (ref "U$32") (pin "3") (pinfunction "3_3") (pintype "bidirectional"))
      (node (ref "U$32") (pin "5") (pinfunction "5_5") (pintype "bidirectional"))
    )
    (net (code "84") (name "Net-(U$27-Pad2)") (class "Default")
      (node (ref "U$27") (pin "2") (pinfunction "2_2") (pintype "bidirectional"))
      (node (ref "U$27") (pin "4") (pinfunction "4_4") (pintype "bidirectional"))
      (node (ref "U$27") (pin "6") (pinfunction "6_6") (pintype "bidirectional"))
      (node (ref "U$33") (pin "1") (pinfunction "1_1") (pintype "bidirectional"))
      (node (ref "U$33") (pin "3") (pinfunction "3_3") (pintype "bidirectional"))
      (node (ref "U$33") (pin "5") (pinfunction "5_5") (pintype "bidirectional"))
    )
    (net (code "85") (name "Net-(U$28-Pad2)") (class "Default")
      (node (ref "U$28") (pin "2") (pinfunction "2_2") (pintype "bidirectional"))
      (node (ref "U$28") (pin "4") (pinfunction "4_4") (pintype "bidirectional"))
      (node (ref "U$28") (pin "6") (pinfunction "6_6") (pintype "bidirectional"))
      (node (ref "U$35") (pin "1") (pinfunction "1_1") (pintype "bidirectional"))
      (node (ref "U$35") (pin "3") (pinfunction "3_3") (pintype "bidirectional"))
      (node (ref "U$35") (pin "5") (pinfunction "5_5") (pintype "bidirectional"))
    )
    (net (code "86") (name "Net-(U$34-Pad2)") (class "Default")
      (node (ref "U$34") (pin "2") (pinfunction "2_2") (pintype "bidirectional"))
      (node (ref "U$38") (pin "1") (pinfunction "1_1") (pintype "bidirectional"))
    )
    (net (code "87") (name "Net-(U$34-Pad4)") (class "Default")
      (node (ref "U$34") (pin "4") (pinfunction "4_4") (pintype "bidirectional"))
      (node (ref "U$38") (pin "3") (pinfunction "3_3") (pintype "bidirectional"))
    )
    (net (code "88") (name "Net-(U$34-Pad6)") (class "Default")
      (node (ref "U$34") (pin "6") (pinfunction "6_6") (pintype "bidirectional"))
      (node (ref "U$38") (pin "5") (pinfunction "5_5") (pintype "bidirectional"))
    )
  )
)
